# ORing_v2.net
KiCad netlist of a schematic drawn in EAGLE
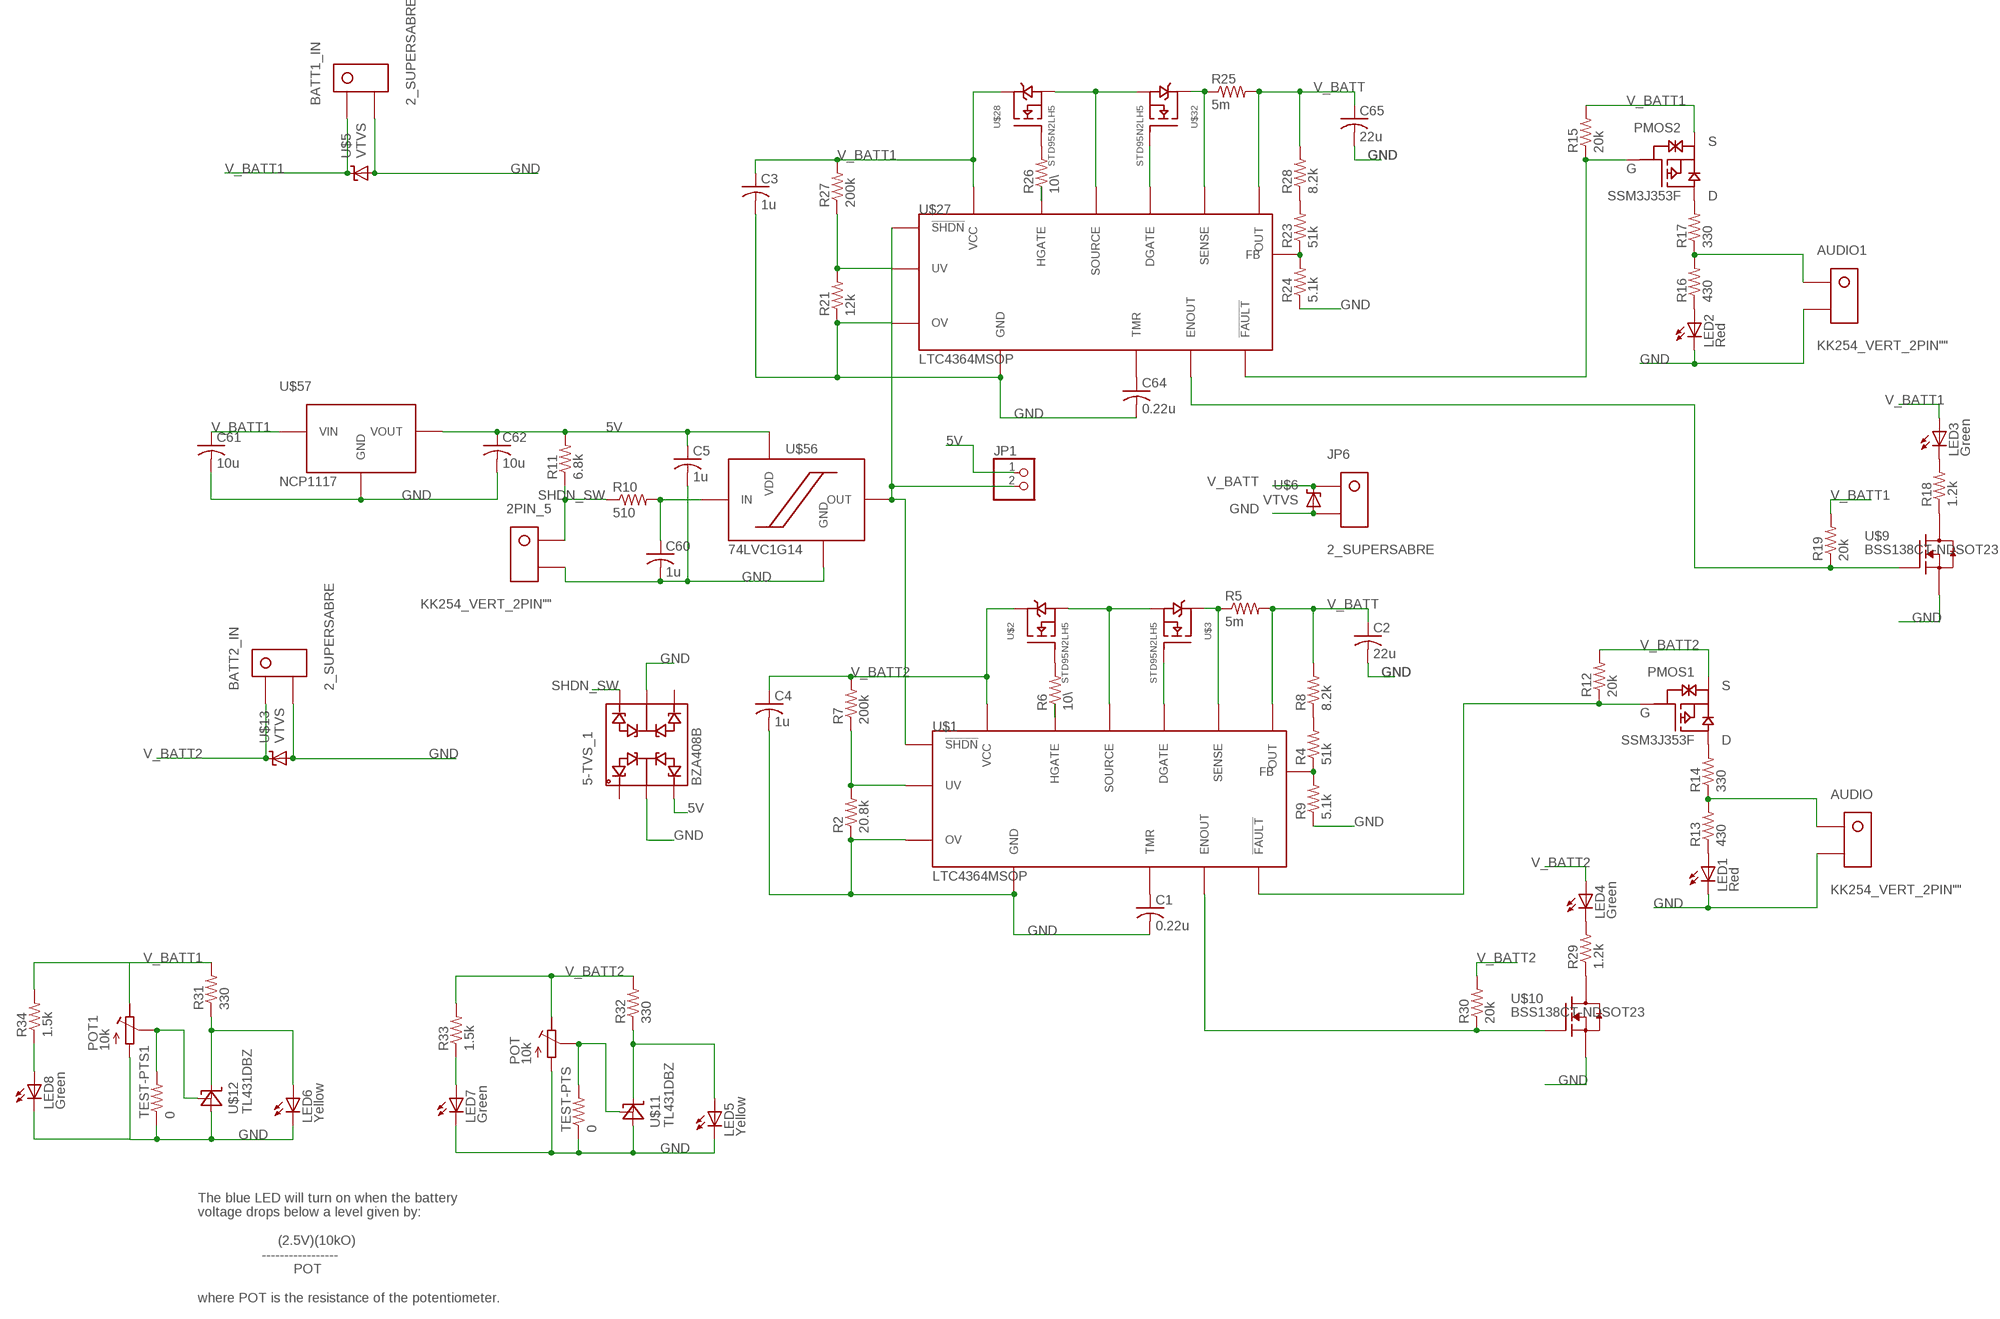
[diagram p0: schematic, sheet 1]

(export (version "E")
  (design (tool "Eeschema 10.0.6"))
  (components
    (comp (ref "2PIN_5")
      (value "KK254_VERT_2PIN\"\"")
      (footprint "eagle-import:KK254_VERT_2PIN")
      (libsource (lib "eagle-import") (part "KK254_VERT_2PIN{dblquote}{dblquote}"))
    )
    (comp (ref "5-TVS_1")
      (value "BZA408B")
      (footprint "eagle-import:SOT457")
      (libsource (lib "eagle-import") (part "BZA408B"))
    )
    (comp (ref "AUDIO")
      (value "KK254_VERT_2PIN\"\"")
      (footprint "eagle-import:KK254_VERT_2PIN")
      (libsource (lib "eagle-import") (part "KK254_VERT_2PIN{dblquote}{dblquote}"))
    )
    (comp (ref "AUDIO1")
      (value "KK254_VERT_2PIN\"\"")
      (footprint "eagle-import:KK254_VERT_2PIN")
      (libsource (lib "eagle-import") (part "KK254_VERT_2PIN{dblquote}{dblquote}"))
    )
    (comp (ref "BATT1_IN")
      (value "2_SUPERSABRE")
      (footprint "eagle-import:SUPERSABRE_2CIRCUIT")
      (libsource (lib "eagle-import") (part "2_SUPERSABRE"))
    )
    (comp (ref "BATT2_IN")
      (value "2_SUPERSABRE")
      (footprint "eagle-import:SUPERSABRE_2CIRCUIT")
      (libsource (lib "eagle-import") (part "2_SUPERSABRE"))
    )
    (comp (ref "C1")
      (value "0.22u")
      (footprint "eagle-import:C0805")
      (libsource (lib "eagle-import") (part "C-USC0805"))
    )
    (comp (ref "C2")
      (value "22u")
      (footprint "eagle-import:C0805")
      (libsource (lib "eagle-import") (part "C-USC0805"))
    )
    (comp (ref "C3")
      (value "1u")
      (footprint "eagle-import:C0805")
      (libsource (lib "eagle-import") (part "C-USC0805"))
    )
    (comp (ref "C4")
      (value "1u")
      (footprint "eagle-import:C0805")
      (libsource (lib "eagle-import") (part "C-USC0805"))
    )
    (comp (ref "C5")
      (value "1u")
      (footprint "eagle-import:C0805")
      (libsource (lib "eagle-import") (part "C-USC0805"))
    )
    (comp (ref "C60")
      (value "1u")
      (footprint "eagle-import:C0805")
      (libsource (lib "eagle-import") (part "C-USC0805"))
    )
    (comp (ref "C61")
      (value "10u")
      (footprint "eagle-import:C0805")
      (libsource (lib "eagle-import") (part "C-USC0805"))
    )
    (comp (ref "C62")
      (value "10u")
      (footprint "eagle-import:C0805")
      (libsource (lib "eagle-import") (part "C-USC0805"))
    )
    (comp (ref "C64")
      (value "0.22u")
      (footprint "eagle-import:C0805")
      (libsource (lib "eagle-import") (part "C-USC0805"))
    )
    (comp (ref "C65")
      (value "22u")
      (footprint "eagle-import:C0805")
      (libsource (lib "eagle-import") (part "C-USC0805"))
    )
    (comp (ref "JP1")
      (value "PINHD-1X2")
      (footprint "eagle-import:1X02")
      (libsource (lib "eagle-import") (part "PINHD-1X2"))
    )
    (comp (ref "JP6")
      (value "2_SUPERSABRE")
      (footprint "eagle-import:SUPERSABRE_2CIRCUIT")
      (libsource (lib "eagle-import") (part "2_SUPERSABRE"))
    )
    (comp (ref "LED1")
      (value "Red")
      (footprint "eagle-import:0805")
      (libsource (lib "eagle-import") (part "0805_LED"))
    )
    (comp (ref "LED2")
      (value "Red")
      (footprint "eagle-import:0805")
      (libsource (lib "eagle-import") (part "0805_LED"))
    )
    (comp (ref "LED3")
      (value "Green")
      (footprint "eagle-import:CHIPLED_0805")
      (libsource (lib "eagle-import") (part "LEDCHIPLED_0805"))
    )
    (comp (ref "LED4")
      (value "Green")
      (footprint "eagle-import:0805")
      (libsource (lib "eagle-import") (part "0805_LED"))
    )
    (comp (ref "LED5")
      (value "Yellow")
      (footprint "eagle-import:0805")
      (libsource (lib "eagle-import") (part "0805_LED"))
    )
    (comp (ref "LED6")
      (value "Yellow")
      (footprint "eagle-import:0805")
      (libsource (lib "eagle-import") (part "0805_LED"))
    )
    (comp (ref "LED7")
      (value "Green")
      (footprint "eagle-import:0805")
      (libsource (lib "eagle-import") (part "0805_LED"))
    )
    (comp (ref "LED8")
      (value "Green")
      (footprint "eagle-import:0805")
      (libsource (lib "eagle-import") (part "0805_LED"))
    )
    (comp (ref "PMOS1")
      (value "SSM3J353F")
      (footprint "eagle-import:SOT-346-3_S-MINI")
      (libsource (lib "eagle-import") (part "SSM3J353F"))
    )
    (comp (ref "PMOS2")
      (value "SSM3J353F")
      (footprint "eagle-import:SOT-346-3_S-MINI")
      (libsource (lib "eagle-import") (part "SSM3J353F"))
    )
    (comp (ref "POT")
      (value "10k")
      (footprint "eagle-import:PTV09A-4")
      (libsource (lib "eagle-import") (part "R-TRIMMPTV09A-4"))
    )
    (comp (ref "POT1")
      (value "10k")
      (footprint "eagle-import:PTV09A-4")
      (libsource (lib "eagle-import") (part "R-TRIMMPTV09A-4"))
    )
    (comp (ref "R2")
      (value "20.8k")
      (footprint "eagle-import:R0805")
      (libsource (lib "eagle-import") (part "R-US_R0805"))
    )
    (comp (ref "R4")
      (value "51k")
      (footprint "eagle-import:R0805")
      (libsource (lib "eagle-import") (part "R-US_R0805"))
    )
    (comp (ref "R5")
      (value "5m")
      (footprint "eagle-import:R0805")
      (libsource (lib "eagle-import") (part "R-US_R0805"))
    )
    (comp (ref "R6")
      (value "10\\")
      (footprint "eagle-import:R0805")
      (libsource (lib "eagle-import") (part "R-US_R0805"))
    )
    (comp (ref "R7")
      (value "200k")
      (footprint "eagle-import:R0805")
      (libsource (lib "eagle-import") (part "R-US_R0805"))
    )
    (comp (ref "R8")
      (value "8.2k")
      (footprint "eagle-import:R0805")
      (libsource (lib "eagle-import") (part "R-US_R0805"))
    )
    (comp (ref "R9")
      (value "5.1k")
      (footprint "eagle-import:R0805")
      (libsource (lib "eagle-import") (part "R-US_R0805"))
    )
    (comp (ref "R10")
      (value "510")
      (footprint "eagle-import:R0805")
      (libsource (lib "eagle-import") (part "R-US_R0805"))
    )
    (comp (ref "R11")
      (value "6.8k")
      (footprint "eagle-import:R0805")
      (libsource (lib "eagle-import") (part "R-US_R0805"))
    )
    (comp (ref "R12")
      (value "20k")
      (footprint "eagle-import:R0805")
      (libsource (lib "eagle-import") (part "R-US_R0805"))
    )
    (comp (ref "R13")
      (value "430")
      (footprint "eagle-import:R0805")
      (libsource (lib "eagle-import") (part "R-US_R0805"))
    )
    (comp (ref "R14")
      (value "330")
      (footprint "eagle-import:R0805")
      (libsource (lib "eagle-import") (part "R-US_R0805"))
    )
    (comp (ref "R15")
      (value "20k")
      (footprint "eagle-import:R0805")
      (libsource (lib "eagle-import") (part "R-US_R0805"))
    )
    (comp (ref "R16")
      (value "430")
      (footprint "eagle-import:R0805")
      (libsource (lib "eagle-import") (part "R-US_R0805"))
    )
    (comp (ref "R17")
      (value "330")
      (footprint "eagle-import:R0805")
      (libsource (lib "eagle-import") (part "R-US_R0805"))
    )
    (comp (ref "R18")
      (value "1.2k")
      (footprint "eagle-import:R0805")
      (libsource (lib "eagle-import") (part "R-US_R0805"))
    )
    (comp (ref "R19")
      (value "20k")
      (footprint "eagle-import:R0805")
      (libsource (lib "eagle-import") (part "R-US_R0805"))
    )
    (comp (ref "R21")
      (value "12k")
      (footprint "eagle-import:R0805")
      (libsource (lib "eagle-import") (part "R-US_R0805"))
    )
    (comp (ref "R23")
      (value "51k")
      (footprint "eagle-import:R0805")
      (libsource (lib "eagle-import") (part "R-US_R0805"))
    )
    (comp (ref "R24")
      (value "5.1k")
      (footprint "eagle-import:R0805")
      (libsource (lib "eagle-import") (part "R-US_R0805"))
    )
    (comp (ref "R25")
      (value "5m")
      (footprint "eagle-import:R0805")
      (libsource (lib "eagle-import") (part "R-US_R0805"))
    )
    (comp (ref "R26")
      (value "10\\")
      (footprint "eagle-import:R0805")
      (libsource (lib "eagle-import") (part "R-US_R0805"))
    )
    (comp (ref "R27")
      (value "200k")
      (footprint "eagle-import:R0805")
      (libsource (lib "eagle-import") (part "R-US_R0805"))
    )
    (comp (ref "R28")
      (value "8.2k")
      (footprint "eagle-import:R0805")
      (libsource (lib "eagle-import") (part "R-US_R0805"))
    )
    (comp (ref "R29")
      (value "1.2k")
      (footprint "eagle-import:R0805")
      (libsource (lib "eagle-import") (part "R-US_R0805"))
    )
    (comp (ref "R30")
      (value "20k")
      (footprint "eagle-import:R0805")
      (libsource (lib "eagle-import") (part "R-US_R0805"))
    )
    (comp (ref "R31")
      (value "330")
      (footprint "eagle-import:R0805")
      (libsource (lib "eagle-import") (part "R-US_R0805"))
    )
    (comp (ref "R32")
      (value "330")
      (footprint "eagle-import:R0805")
      (libsource (lib "eagle-import") (part "R-US_R0805"))
    )
    (comp (ref "R33")
      (value "1.5k")
      (footprint "eagle-import:R0805")
      (libsource (lib "eagle-import") (part "R-US_R0805"))
    )
    (comp (ref "R34")
      (value "1.5k")
      (footprint "eagle-import:R0805")
      (libsource (lib "eagle-import") (part "R-US_R0805"))
    )
    (comp (ref "TEST-PTS")
      (value "0")
      (footprint "eagle-import:V526-0")
      (libsource (lib "eagle-import") (part "R-US_V526-0"))
    )
    (comp (ref "TEST-PTS1")
      (value "0")
      (footprint "eagle-import:V526-0")
      (libsource (lib "eagle-import") (part "R-US_V526-0"))
    )
    (comp (ref "U$1")
      (value "LTC4364MSOP")
      (footprint "eagle-import:MSOP16")
      (libsource (lib "eagle-import") (part "LTC4364MSOP"))
    )
    (comp (ref "U$2")
      (value "STD95N2LH5")
      (footprint "eagle-import:DPAK")
      (libsource (lib "eagle-import") (part "STD95N2LH5"))
    )
    (comp (ref "U$3")
      (value "STD95N2LH5")
      (footprint "eagle-import:DPAK")
      (libsource (lib "eagle-import") (part "STD95N2LH5"))
    )
    (comp (ref "U$5")
      (value "VTVS")
      (footprint "eagle-import:DO-219AB")
      (libsource (lib "eagle-import") (part "VTVS"))
    )
    (comp (ref "U$6")
      (value "VTVS")
      (footprint "eagle-import:DO-219AB")
      (libsource (lib "eagle-import") (part "VTVS"))
    )
    (comp (ref "U$9")
      (value "BSS138CT-NDSOT23")
      (footprint "eagle-import:SOT23")
      (libsource (lib "eagle-import") (part "BSS138CT-NDSOT23"))
    )
    (comp (ref "U$10")
      (value "BSS138CT-NDSOT23")
      (footprint "eagle-import:SOT23")
      (libsource (lib "eagle-import") (part "BSS138CT-NDSOT23"))
    )
    (comp (ref "U$11")
      (value "TL431DBZ")
      (footprint "eagle-import:SOT-23-3")
      (libsource (lib "eagle-import") (part "TL431DBZ"))
    )
    (comp (ref "U$12")
      (value "TL431DBZ")
      (footprint "eagle-import:SOT-23-3")
      (libsource (lib "eagle-import") (part "TL431DBZ"))
    )
    (comp (ref "U$13")
      (value "VTVS")
      (footprint "eagle-import:DO-219AB")
      (libsource (lib "eagle-import") (part "VTVS"))
    )
    (comp (ref "U$27")
      (value "LTC4364MSOP")
      (footprint "eagle-import:MSOP16")
      (libsource (lib "eagle-import") (part "LTC4364MSOP"))
    )
    (comp (ref "U$28")
      (value "STD95N2LH5")
      (footprint "eagle-import:DPAK")
      (libsource (lib "eagle-import") (part "STD95N2LH5"))
    )
    (comp (ref "U$32")
      (value "STD95N2LH5")
      (footprint "eagle-import:DPAK")
      (libsource (lib "eagle-import") (part "STD95N2LH5"))
    )
    (comp (ref "U$56")
      (value "74LVC1G14")
      (footprint "eagle-import:TSSOP5")
      (libsource (lib "eagle-import") (part "74LVC1G14"))
    )
    (comp (ref "U$57")
      (value "NCP1117")
      (footprint "eagle-import:SOT-223")
      (libsource (lib "eagle-import") (part "NCP1117"))
    )
  )
  (nets
    (net (code "1") (name "/5V") (class "Default")
      (node (ref "5-TVS_1") (pin "P$3") (pinfunction "P$3_P$3") (pintype "bidirectional"))
      (node (ref "C5") (pin "1") (pinfunction "1_1") (pintype "passive"))
      (node (ref "C62") (pin "1") (pinfunction "1_1") (pintype "passive"))
      (node (ref "JP1") (pin "1") (pinfunction "1_1") (pintype "passive"))
      (node (ref "R11") (pin "2") (pinfunction "2_2") (pintype "passive"))
      (node (ref "U$56") (pin "P$5") (pinfunction "VDD_P$5") (pintype "bidirectional"))
      (node (ref "U$57") (pin "P$2") (pinfunction "VOUT_P$2") (pintype "bidirectional"))
      (node (ref "U$57") (pin "P$4") (pinfunction "VOUT_P$4") (pintype "bidirectional"))
    )
    (net (code "2") (name "/GND") (class "Default")
      (node (ref "2PIN_5") (pin "P$2") (pinfunction "P$2_P$2") (pintype "bidirectional"))
      (node (ref "5-TVS_1") (pin "P$2") (pinfunction "P$2_P$2") (pintype "bidirectional"))
      (node (ref "5-TVS_1") (pin "P$5") (pinfunction "P$5_P$5") (pintype "bidirectional"))
      (node (ref "AUDIO") (pin "P$2") (pinfunction "P$2_P$2") (pintype "bidirectional"))
      (node (ref "AUDIO1") (pin "P$2") (pinfunction "P$2_P$2") (pintype "bidirectional"))
      (node (ref "BATT1_IN") (pin "P$2") (pinfunction "P$2_P$2") (pintype "bidirectional"))
      (node (ref "BATT2_IN") (pin "P$2") (pinfunction "P$2_P$2") (pintype "bidirectional"))
      (node (ref "C1") (pin "2") (pinfunction "2_2") (pintype "passive"))
      (node (ref "C2") (pin "2") (pinfunction "2_2") (pintype "passive"))
      (node (ref "C3") (pin "2") (pinfunction "2_2") (pintype "passive"))
      (node (ref "C4") (pin "2") (pinfunction "2_2") (pintype "passive"))
      (node (ref "C5") (pin "2") (pinfunction "2_2") (pintype "passive"))
      (node (ref "C60") (pin "2") (pinfunction "2_2") (pintype "passive"))
      (node (ref "C61") (pin "2") (pinfunction "2_2") (pintype "passive"))
      (node (ref "C62") (pin "2") (pinfunction "2_2") (pintype "passive"))
      (node (ref "C64") (pin "2") (pinfunction "2_2") (pintype "passive"))
      (node (ref "C65") (pin "2") (pinfunction "2_2") (pintype "passive"))
      (node (ref "JP6") (pin "P$2") (pinfunction "P$2_P$2") (pintype "bidirectional"))
      (node (ref "LED1") (pin "P$2") (pinfunction "C_P$2") (pintype "passive"))
      (node (ref "LED2") (pin "P$2") (pinfunction "C_P$2") (pintype "passive"))
      (node (ref "LED5") (pin "P$2") (pinfunction "C_P$2") (pintype "passive"))
      (node (ref "LED6") (pin "P$2") (pinfunction "C_P$2") (pintype "passive"))
      (node (ref "LED7") (pin "P$2") (pinfunction "C_P$2") (pintype "passive"))
      (node (ref "LED8") (pin "P$2") (pinfunction "C_P$2") (pintype "passive"))
      (node (ref "POT") (pin "P$3") (pinfunction "E_P$3") (pintype "passive"))
      (node (ref "POT1") (pin "P$3") (pinfunction "E_P$3") (pintype "passive"))
      (node (ref "R2") (pin "1") (pinfunction "1_1") (pintype "passive"))
      (node (ref "R21") (pin "1") (pinfunction "1_1") (pintype "passive"))
      (node (ref "R24") (pin "1") (pinfunction "1_1") (pintype "passive"))
      (node (ref "R9") (pin "1") (pinfunction "1_1") (pintype "passive"))
      (node (ref "TEST-PTS") (pin "1") (pinfunction "1_1") (pintype "passive"))
      (node (ref "TEST-PTS1") (pin "1") (pinfunction "1_1") (pintype "passive"))
      (node (ref "U$1") (pin "GND") (pinfunction "GND_GND") (pintype "bidirectional"))
      (node (ref "U$1") (pin "OV") (pinfunction "OV_OV") (pintype "bidirectional"))
      (node (ref "U$10") (pin "2") (pinfunction "S_2") (pintype "passive"))
      (node (ref "U$11") (pin "P$3") (pinfunction "A_P$3") (pintype "passive"))
      (node (ref "U$12") (pin "P$3") (pinfunction "A_P$3") (pintype "passive"))
      (node (ref "U$13") (pin "P$1") (pinfunction "A_P$1") (pintype "passive"))
      (node (ref "U$27") (pin "GND") (pinfunction "GND_GND") (pintype "bidirectional"))
      (node (ref "U$27") (pin "OV") (pinfunction "OV_OV") (pintype "bidirectional"))
      (node (ref "U$5") (pin "P$1") (pinfunction "A_P$1") (pintype "passive"))
      (node (ref "U$56") (pin "P$3") (pinfunction "GND_P$3") (pintype "bidirectional"))
      (node (ref "U$57") (pin "P$1") (pinfunction "GND_P$1") (pintype "bidirectional"))
      (node (ref "U$6") (pin "P$1") (pinfunction "A_P$1") (pintype "passive"))
      (node (ref "U$9") (pin "2") (pinfunction "S_2") (pintype "passive"))
    )
    (net (code "3") (name "/SHDN_SW") (class "Default")
      (node (ref "2PIN_5") (pin "P$1") (pinfunction "P$1_P$1") (pintype "bidirectional"))
      (node (ref "5-TVS_1") (pin "P$6") (pinfunction "P$6_P$6") (pintype "bidirectional"))
      (node (ref "R10") (pin "1") (pinfunction "1_1") (pintype "passive"))
      (node (ref "R11") (pin "1") (pinfunction "1_1") (pintype "passive"))
    )
    (net (code "4") (name "/V_BATT") (class "Default")
      (node (ref "C2") (pin "1") (pinfunction "1_1") (pintype "passive"))
      (node (ref "C65") (pin "1") (pinfunction "1_1") (pintype "passive"))
      (node (ref "JP6") (pin "P$1") (pinfunction "P$1_P$1") (pintype "bidirectional"))
      (node (ref "R25") (pin "2") (pinfunction "2_2") (pintype "passive"))
      (node (ref "R28") (pin "2") (pinfunction "2_2") (pintype "passive"))
      (node (ref "R5") (pin "2") (pinfunction "2_2") (pintype "passive"))
      (node (ref "R8") (pin "2") (pinfunction "2_2") (pintype "passive"))
      (node (ref "U$1") (pin "OUT") (pinfunction "OUT_OUT") (pintype "bidirectional"))
      (node (ref "U$27") (pin "OUT") (pinfunction "OUT_OUT") (pintype "bidirectional"))
      (node (ref "U$6") (pin "P$2") (pinfunction "C_P$2") (pintype "passive"))
    )
    (net (code "5") (name "/V_BATT1") (class "Default")
      (node (ref "BATT1_IN") (pin "P$1") (pinfunction "P$1_P$1") (pintype "bidirectional"))
      (node (ref "C3") (pin "1") (pinfunction "1_1") (pintype "passive"))
      (node (ref "C61") (pin "1") (pinfunction "1_1") (pintype "passive"))
      (node (ref "LED3") (pin "A") (pinfunction "A_A") (pintype "passive"))
      (node (ref "PMOS2") (pin "P$3") (pinfunction "S_P$3") (pintype "bidirectional"))
      (node (ref "POT1") (pin "P$1") (pinfunction "A_P$1") (pintype "passive"))
      (node (ref "R15") (pin "2") (pinfunction "2_2") (pintype "passive"))
      (node (ref "R19") (pin "2") (pinfunction "2_2") (pintype "passive"))
      (node (ref "R27") (pin "2") (pinfunction "2_2") (pintype "passive"))
      (node (ref "R31") (pin "2") (pinfunction "2_2") (pintype "passive"))
      (node (ref "R34") (pin "2") (pinfunction "2_2") (pintype "passive"))
      (node (ref "U$27") (pin "VCC") (pinfunction "VCC_VCC") (pintype "bidirectional"))
      (node (ref "U$28") (pin "TAB") (pinfunction "D_TAB") (pintype "bidirectional"))
      (node (ref "U$5") (pin "P$2") (pinfunction "C_P$2") (pintype "passive"))
      (node (ref "U$57") (pin "P$3") (pinfunction "VIN_P$3") (pintype "bidirectional"))
    )
    (net (code "6") (name "/V_BATT2") (class "Default")
      (node (ref "BATT2_IN") (pin "P$1") (pinfunction "P$1_P$1") (pintype "bidirectional"))
      (node (ref "C4") (pin "1") (pinfunction "1_1") (pintype "passive"))
      (node (ref "LED4") (pin "P$1") (pinfunction "A_P$1") (pintype "passive"))
      (node (ref "PMOS1") (pin "P$3") (pinfunction "S_P$3") (pintype "bidirectional"))
      (node (ref "POT") (pin "P$1") (pinfunction "A_P$1") (pintype "passive"))
      (node (ref "R12") (pin "2") (pinfunction "2_2") (pintype "passive"))
      (node (ref "R30") (pin "2") (pinfunction "2_2") (pintype "passive"))
      (node (ref "R32") (pin "2") (pinfunction "2_2") (pintype "passive"))
      (node (ref "R33") (pin "2") (pinfunction "2_2") (pintype "passive"))
      (node (ref "R7") (pin "2") (pinfunction "2_2") (pintype "passive"))
      (node (ref "U$1") (pin "VCC") (pinfunction "VCC_VCC") (pintype "bidirectional"))
      (node (ref "U$13") (pin "P$2") (pinfunction "C_P$2") (pintype "passive"))
      (node (ref "U$2") (pin "TAB") (pinfunction "D_TAB") (pintype "bidirectional"))
    )
    (net (code "7") (name "Net-(AUDIO-PadP$1)") (class "Default")
      (node (ref "AUDIO") (pin "P$1") (pinfunction "P$1_P$1") (pintype "bidirectional"))
      (node (ref "R13") (pin "2") (pinfunction "2_2") (pintype "passive"))
      (node (ref "R14") (pin "1") (pinfunction "1_1") (pintype "passive"))
    )
    (net (code "8") (name "Net-(AUDIO1-PadP$1)") (class "Default")
      (node (ref "AUDIO1") (pin "P$1") (pinfunction "P$1_P$1") (pintype "bidirectional"))
      (node (ref "R16") (pin "2") (pinfunction "2_2") (pintype "passive"))
      (node (ref "R17") (pin "1") (pinfunction "1_1") (pintype "passive"))
    )
    (net (code "9") (name "Net-(C1-Pad1)") (class "Default")
      (node (ref "C1") (pin "1") (pinfunction "1_1") (pintype "passive"))
      (node (ref "U$1") (pin "TMR") (pinfunction "TMR_TMR") (pintype "bidirectional"))
    )
    (net (code "10") (name "Net-(C64-Pad1)") (class "Default")
      (node (ref "C64") (pin "1") (pinfunction "1_1") (pintype "passive"))
      (node (ref "U$27") (pin "TMR") (pinfunction "TMR_TMR") (pintype "bidirectional"))
    )
    (net (code "11") (name "Net-(LED1-A)") (class "Default")
      (node (ref "LED1") (pin "P$1") (pinfunction "A_P$1") (pintype "passive"))
      (node (ref "R13") (pin "1") (pinfunction "1_1") (pintype "passive"))
    )
    (net (code "12") (name "Net-(LED2-A)") (class "Default")
      (node (ref "LED2") (pin "P$1") (pinfunction "A_P$1") (pintype "passive"))
      (node (ref "R16") (pin "1") (pinfunction "1_1") (pintype "passive"))
    )
    (net (code "13") (name "Net-(LED3-PadC)") (class "Default")
      (node (ref "LED3") (pin "C") (pinfunction "C_C") (pintype "passive"))
      (node (ref "R18") (pin "2") (pinfunction "2_2") (pintype "passive"))
    )
    (net (code "14") (name "Net-(LED4-C)") (class "Default")
      (node (ref "LED4") (pin "P$2") (pinfunction "C_P$2") (pintype "passive"))
      (node (ref "R29") (pin "2") (pinfunction "2_2") (pintype "passive"))
    )
    (net (code "15") (name "Net-(LED5-A)") (class "Default")
      (node (ref "LED5") (pin "P$1") (pinfunction "A_P$1") (pintype "passive"))
      (node (ref "R32") (pin "1") (pinfunction "1_1") (pintype "passive"))
      (node (ref "U$11") (pin "P$1") (pinfunction "C_P$1") (pintype "passive"))
    )
    (net (code "16") (name "Net-(LED6-A)") (class "Default")
      (node (ref "LED6") (pin "P$1") (pinfunction "A_P$1") (pintype "passive"))
      (node (ref "R31") (pin "1") (pinfunction "1_1") (pintype "passive"))
      (node (ref "U$12") (pin "P$1") (pinfunction "C_P$1") (pintype "passive"))
    )
    (net (code "17") (name "Net-(LED7-A)") (class "Default")
      (node (ref "LED7") (pin "P$1") (pinfunction "A_P$1") (pintype "passive"))
      (node (ref "R33") (pin "1") (pinfunction "1_1") (pintype "passive"))
    )
    (net (code "18") (name "Net-(LED8-A)") (class "Default")
      (node (ref "LED8") (pin "P$1") (pinfunction "A_P$1") (pintype "passive"))
      (node (ref "R34") (pin "1") (pinfunction "1_1") (pintype "passive"))
    )
    (net (code "19") (name "Net-(PMOS1-D)") (class "Default")
      (node (ref "PMOS1") (pin "P$2") (pinfunction "D_P$2") (pintype "bidirectional"))
      (node (ref "R14") (pin "2") (pinfunction "2_2") (pintype "passive"))
    )
    (net (code "20") (name "Net-(PMOS1-G)") (class "Default")
      (node (ref "PMOS1") (pin "P$1") (pinfunction "G_P$1") (pintype "bidirectional"))
      (node (ref "R12") (pin "1") (pinfunction "1_1") (pintype "passive"))
      (node (ref "U$1") (pin "FLT") (pinfunction "~{FAULT}_FLT") (pintype "bidirectional"))
    )
    (net (code "21") (name "Net-(PMOS2-D)") (class "Default")
      (node (ref "PMOS2") (pin "P$2") (pinfunction "D_P$2") (pintype "bidirectional"))
      (node (ref "R17") (pin "2") (pinfunction "2_2") (pintype "passive"))
    )
    (net (code "22") (name "Net-(PMOS2-G)") (class "Default")
      (node (ref "PMOS2") (pin "P$1") (pinfunction "G_P$1") (pintype "bidirectional"))
      (node (ref "R15") (pin "1") (pinfunction "1_1") (pintype "passive"))
      (node (ref "U$27") (pin "FLT") (pinfunction "~{FAULT}_FLT") (pintype "bidirectional"))
    )
    (net (code "23") (name "Net-(POT-S)") (class "Default")
      (node (ref "POT") (pin "P$2") (pinfunction "S_P$2") (pintype "passive"))
      (node (ref "TEST-PTS") (pin "2") (pinfunction "2_2") (pintype "passive"))
      (node (ref "U$11") (pin "P$2") (pinfunction "REF_P$2") (pintype "bidirectional"))
    )
    (net (code "24") (name "Net-(POT1-S)") (class "Default")
      (node (ref "POT1") (pin "P$2") (pinfunction "S_P$2") (pintype "passive"))
      (node (ref "TEST-PTS1") (pin "2") (pinfunction "2_2") (pintype "passive"))
      (node (ref "U$12") (pin "P$2") (pinfunction "REF_P$2") (pintype "bidirectional"))
    )
    (net (code "25") (name "Net-(R2-Pad2)") (class "Default")
      (node (ref "R2") (pin "2") (pinfunction "2_2") (pintype "passive"))
      (node (ref "R7") (pin "1") (pinfunction "1_1") (pintype "passive"))
      (node (ref "U$1") (pin "UV") (pinfunction "UV_UV") (pintype "bidirectional"))
    )
    (net (code "26") (name "Net-(R4-Pad1)") (class "Default")
      (node (ref "R4") (pin "1") (pinfunction "1_1") (pintype "passive"))
      (node (ref "R9") (pin "2") (pinfunction "2_2") (pintype "passive"))
      (node (ref "U$1") (pin "FB") (pinfunction "FB_FB") (pintype "bidirectional"))
    )
    (net (code "27") (name "Net-(R4-Pad2)") (class "Default")
      (node (ref "R4") (pin "2") (pinfunction "2_2") (pintype "passive"))
      (node (ref "R8") (pin "1") (pinfunction "1_1") (pintype "passive"))
    )
    (net (code "28") (name "Net-(R6-Pad1)") (class "Default")
      (node (ref "R6") (pin "1") (pinfunction "1_1") (pintype "passive"))
      (node (ref "U$1") (pin "HGATE") (pinfunction "HGATE_HGATE") (pintype "bidirectional"))
    )
    (net (code "29") (name "Net-(R21-Pad2)") (class "Default")
      (node (ref "R21") (pin "2") (pinfunction "2_2") (pintype "passive"))
      (node (ref "R27") (pin "1") (pinfunction "1_1") (pintype "passive"))
      (node (ref "U$27") (pin "UV") (pinfunction "UV_UV") (pintype "bidirectional"))
    )
    (net (code "30") (name "Net-(R23-Pad1)") (class "Default")
      (node (ref "R23") (pin "1") (pinfunction "1_1") (pintype "passive"))
      (node (ref "R24") (pin "2") (pinfunction "2_2") (pintype "passive"))
      (node (ref "U$27") (pin "FB") (pinfunction "FB_FB") (pintype "bidirectional"))
    )
    (net (code "31") (name "Net-(R23-Pad2)") (class "Default")
      (node (ref "R23") (pin "2") (pinfunction "2_2") (pintype "passive"))
      (node (ref "R28") (pin "1") (pinfunction "1_1") (pintype "passive"))
    )
    (net (code "32") (name "Net-(R26-Pad1)") (class "Default")
      (node (ref "R26") (pin "1") (pinfunction "1_1") (pintype "passive"))
      (node (ref "U$27") (pin "HGATE") (pinfunction "HGATE_HGATE") (pintype "bidirectional"))
    )
    (net (code "33") (name "Net-(U$1-~{SHDN})") (class "Default")
      (node (ref "JP1") (pin "2") (pinfunction "2_2") (pintype "passive"))
      (node (ref "U$1") (pin "SHDN") (pinfunction "~{SHDN}_SHDN") (pintype "bidirectional"))
      (node (ref "U$27") (pin "SHDN") (pinfunction "~{SHDN}_SHDN") (pintype "bidirectional"))
      (node (ref "U$56") (pin "P$4") (pinfunction "OUT_P$4") (pintype "bidirectional"))
    )
    (net (code "34") (name "Net-(U$2-G)") (class "Default")
      (node (ref "R6") (pin "2") (pinfunction "2_2") (pintype "passive"))
      (node (ref "U$2") (pin "1") (pinfunction "G_1") (pintype "bidirectional"))
    )
    (net (code "35") (name "Net-(U$2-S)") (class "Default")
      (node (ref "U$1") (pin "SOURCE") (pinfunction "SOURCE_SOURCE") (pintype "bidirectional"))
      (node (ref "U$2") (pin "3") (pinfunction "S_3") (pintype "bidirectional"))
      (node (ref "U$3") (pin "3") (pinfunction "S_3") (pintype "bidirectional"))
    )
    (net (code "36") (name "Net-(U$3-D)") (class "Default")
      (node (ref "R5") (pin "1") (pinfunction "1_1") (pintype "passive"))
      (node (ref "U$1") (pin "SENSE") (pinfunction "SENSE_SENSE") (pintype "bidirectional"))
      (node (ref "U$3") (pin "TAB") (pinfunction "D_TAB") (pintype "bidirectional"))
    )
    (net (code "37") (name "Net-(U$3-G)") (class "Default")
      (node (ref "U$1") (pin "DGATE") (pinfunction "DGATE_DGATE") (pintype "bidirectional"))
      (node (ref "U$3") (pin "1") (pinfunction "G_1") (pintype "bidirectional"))
    )
    (net (code "38") (name "Net-(U$9-D)") (class "Default")
      (node (ref "R18") (pin "1") (pinfunction "1_1") (pintype "passive"))
      (node (ref "U$9") (pin "3") (pinfunction "D_3") (pintype "bidirectional"))
    )
    (net (code "39") (name "Net-(U$9-G)") (class "Default")
      (node (ref "R19") (pin "1") (pinfunction "1_1") (pintype "passive"))
      (node (ref "U$27") (pin "ENOUT") (pinfunction "ENOUT_ENOUT") (pintype "bidirectional"))
      (node (ref "U$9") (pin "1") (pinfunction "G_1") (pintype "passive"))
    )
    (net (code "40") (name "Net-(U$10-D)") (class "Default")
      (node (ref "R29") (pin "1") (pinfunction "1_1") (pintype "passive"))
      (node (ref "U$10") (pin "3") (pinfunction "D_3") (pintype "bidirectional"))
    )
    (net (code "41") (name "Net-(U$10-G)") (class "Default")
      (node (ref "R30") (pin "1") (pinfunction "1_1") (pintype "passive"))
      (node (ref "U$1") (pin "ENOUT") (pinfunction "ENOUT_ENOUT") (pintype "bidirectional"))
      (node (ref "U$10") (pin "1") (pinfunction "G_1") (pintype "passive"))
    )
    (net (code "42") (name "Net-(U$28-G)") (class "Default")
      (node (ref "R26") (pin "2") (pinfunction "2_2") (pintype "passive"))
      (node (ref "U$28") (pin "1") (pinfunction "G_1") (pintype "bidirectional"))
    )
    (net (code "43") (name "Net-(U$28-S)") (class "Default")
      (node (ref "U$27") (pin "SOURCE") (pinfunction "SOURCE_SOURCE") (pintype "bidirectional"))
      (node (ref "U$28") (pin "3") (pinfunction "S_3") (pintype "bidirectional"))
      (node (ref "U$32") (pin "3") (pinfunction "S_3") (pintype "bidirectional"))
    )
    (net (code "44") (name "Net-(U$32-D)") (class "Default")
      (node (ref "R25") (pin "1") (pinfunction "1_1") (pintype "passive"))
      (node (ref "U$27") (pin "SENSE") (pinfunction "SENSE_SENSE") (pintype "bidirectional"))
      (node (ref "U$32") (pin "TAB") (pinfunction "D_TAB") (pintype "bidirectional"))
    )
    (net (code "45") (name "Net-(U$32-G)") (class "Default")
      (node (ref "U$27") (pin "DGATE") (pinfunction "DGATE_DGATE") (pintype "bidirectional"))
      (node (ref "U$32") (pin "1") (pinfunction "G_1") (pintype "bidirectional"))
    )
    (net (code "46") (name "Net-(U$56-IN)") (class "Default")
      (node (ref "C60") (pin "1") (pinfunction "1_1") (pintype "passive"))
      (node (ref "R10") (pin "2") (pinfunction "2_2") (pintype "passive"))
      (node (ref "U$56") (pin "P$2") (pinfunction "IN_P$2") (pintype "bidirectional"))
    )
    (net (code "47") (name "unconnected-(5-TVS_1-PadP$1)") (class "Default")
      (node (ref "5-TVS_1") (pin "P$1") (pinfunction "P$1_P$1") (pintype "bidirectional"))
    )
    (net (code "48") (name "unconnected-(5-TVS_1-PadP$4)") (class "Default")
      (node (ref "5-TVS_1") (pin "P$4") (pinfunction "P$4_P$4") (pintype "bidirectional"))
    )
  )
)
